# RomWriter.net
KiCad netlist of a schematic drawn in EAGLE
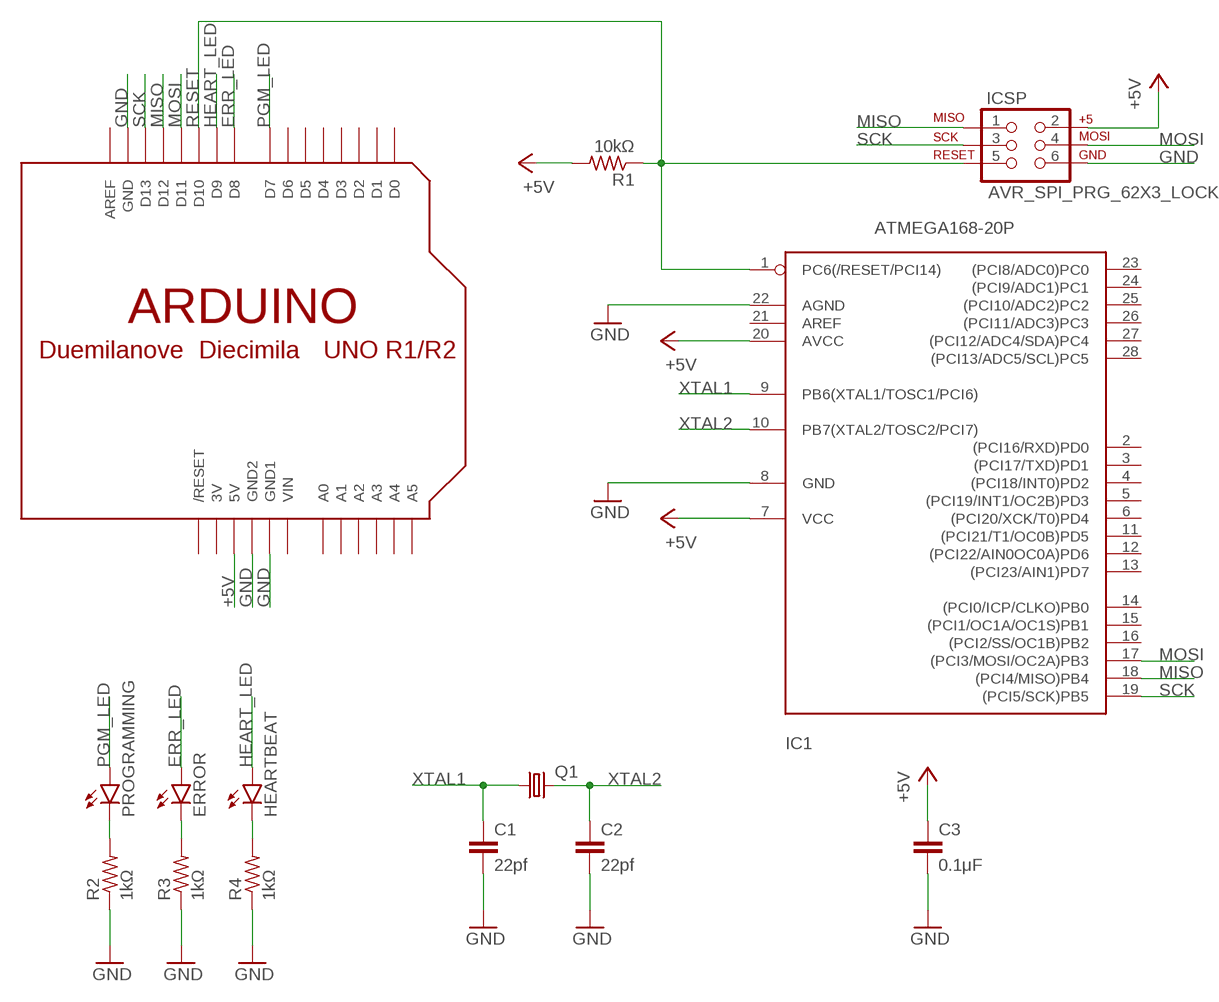
[diagram p0: schematic, sheet 1]

(export (version "E")
  (design (tool "Eeschema 10.0.6"))
  (components
    (comp (ref "C1")
      (value "22pf")
      (footprint "eagle-import:C2.5-2")
      (libsource (lib "eagle-import") (part "C2.5/2"))
    )
    (comp (ref "C2")
      (value "22pf")
      (footprint "eagle-import:C2.5-2")
      (libsource (lib "eagle-import") (part "C2.5/2"))
    )
    (comp (ref "C3")
      (value "0.1μF")
      (footprint "eagle-import:C2.5-2")
      (libsource (lib "eagle-import") (part "C2.5/2"))
    )
    (comp (ref "ERROR")
      (value "LED3MM")
      (footprint "eagle-import:LED3MM")
      (libsource (lib "eagle-import") (part "LED3MM"))
    )
    (comp (ref "HEARTBEAT")
      (value "LED3MM")
      (footprint "eagle-import:LED3MM")
      (libsource (lib "eagle-import") (part "LED3MM"))
    )
    (comp (ref "IC1")
      (value "ATMEGA168-20P")
      (footprint "eagle-import:DIL28-3")
      (libsource (lib "eagle-import") (part "ATMEGA168P-20"))
    )
    (comp (ref "ICSP")
      (value "AVR_SPI_PRG_62X3_LOCK")
      (footprint "eagle-import:2X3_LOCK")
      (libsource (lib "eagle-import") (part "AVR_SPI_PRG_62X3_LOCK"))
    )
    (comp (ref "PROGRAMMING")
      (value "LED3MM")
      (footprint "eagle-import:LED3MM")
      (libsource (lib "eagle-import") (part "LED3MM"))
    )
    (comp (ref "Q1")
      (value "CRYSTALHC49S")
      (footprint "eagle-import:HC49_S")
      (libsource (lib "eagle-import") (part "CRYSTALHC49S"))
    )
    (comp (ref "R1")
      (value "10kΩ")
      (footprint "eagle-import:0805-THM")
      (libsource (lib "eagle-import") (part "FLIPFLOP-RES"))
    )
    (comp (ref "R2")
      (value "1kΩ")
      (footprint "eagle-import:0805-THM")
      (libsource (lib "eagle-import") (part "FLIPFLOP-RES"))
    )
    (comp (ref "R3")
      (value "1kΩ")
      (footprint "eagle-import:0805-THM")
      (libsource (lib "eagle-import") (part "FLIPFLOP-RES"))
    )
    (comp (ref "R4")
      (value "1kΩ")
      (footprint "eagle-import:0805-THM")
      (libsource (lib "eagle-import") (part "FLIPFLOP-RES"))
    )
    (comp (ref "U$1")
      (value "ARDUINO_SHIELD_VER2")
      (footprint "eagle-import:ARDUINO_SHIELD")
      (libsource (lib "eagle-import") (part "ARDUINO_SHIELD_VER2"))
    )
  )
  (nets
    (net (code "1") (name "+5V") (class "Default")
      (node (ref "C3") (pin "1") (pinfunction "1_1") (pintype "passive"))
      (node (ref "IC1") (pin "20") (pinfunction "AVCC_20") (pintype "bidirectional"))
      (node (ref "IC1") (pin "7") (pinfunction "VCC_7") (pintype "bidirectional"))
      (node (ref "ICSP") (pin "2") (pinfunction "2_2") (pintype "passive"))
      (node (ref "R1") (pin "2") (pinfunction "2_2") (pintype "passive"))
      (node (ref "U$1") (pin "5V") (pinfunction "5V_5V") (pintype "power_in"))
    )
    (net (code "2") (name "/3V") (class "Default")
      (node (ref "U$1") (pin "3V") (pinfunction "3V_3V") (pintype "power_in"))
    )
    (net (code "3") (name "/ERR_LED") (class "Default")
      (node (ref "ERROR") (pin "A") (pinfunction "A_A") (pintype "passive"))
      (node (ref "U$1") (pin "D8") (pinfunction "D8_D8") (pintype "bidirectional"))
    )
    (net (code "4") (name "/HEART_LED") (class "Default")
      (node (ref "HEARTBEAT") (pin "A") (pinfunction "A_A") (pintype "passive"))
      (node (ref "U$1") (pin "D9") (pinfunction "D9_D9") (pintype "bidirectional"))
    )
    (net (code "5") (name "/MISO") (class "Default")
      (node (ref "IC1") (pin "18") (pinfunction "(PCI4/MISO)PB4_18") (pintype "bidirectional"))
      (node (ref "ICSP") (pin "1") (pinfunction "1_1") (pintype "passive"))
      (node (ref "U$1") (pin "D12") (pinfunction "D12_D12") (pintype "bidirectional"))
    )
    (net (code "6") (name "/MOSI") (class "Default")
      (node (ref "IC1") (pin "17") (pinfunction "(PCI3/MOSI/OC2A)PB3_17") (pintype "bidirectional"))
      (node (ref "ICSP") (pin "4") (pinfunction "4_4") (pintype "passive"))
      (node (ref "U$1") (pin "D11") (pinfunction "D11_D11") (pintype "bidirectional"))
    )
    (net (code "7") (name "/PGM_LED") (class "Default")
      (node (ref "PROGRAMMING") (pin "A") (pinfunction "A_A") (pintype "passive"))
      (node (ref "U$1") (pin "D7") (pinfunction "D7_D7") (pintype "bidirectional"))
    )
    (net (code "8") (name "/RESET") (class "Default")
      (node (ref "IC1") (pin "1") (pinfunction "PC6(/RESET/PCI14)_1") (pintype "bidirectional"))
      (node (ref "ICSP") (pin "5") (pinfunction "5_5") (pintype "passive"))
      (node (ref "R1") (pin "1") (pinfunction "1_1") (pintype "passive"))
      (node (ref "U$1") (pin "D10") (pinfunction "D10_D10") (pintype "bidirectional"))
    )
    (net (code "9") (name "/SCK") (class "Default")
      (node (ref "IC1") (pin "19") (pinfunction "(PCI5/SCK)PB5_19") (pintype "bidirectional"))
      (node (ref "ICSP") (pin "3") (pinfunction "3_3") (pintype "passive"))
      (node (ref "U$1") (pin "D13") (pinfunction "D13_D13") (pintype "bidirectional"))
    )
    (net (code "10") (name "/VIN") (class "Default")
      (node (ref "U$1") (pin "VIN") (pinfunction "VIN_VIN") (pintype "power_in"))
    )
    (net (code "11") (name "/XTAL1") (class "Default")
      (node (ref "C1") (pin "1") (pinfunction "1_1") (pintype "passive"))
      (node (ref "IC1") (pin "9") (pinfunction "PB6(XTAL1/TOSC1/PCI6)_9") (pintype "bidirectional"))
      (node (ref "Q1") (pin "1") (pinfunction "1_1") (pintype "passive"))
    )
    (net (code "12") (name "/XTAL2") (class "Default")
      (node (ref "C2") (pin "1") (pinfunction "1_1") (pintype "passive"))
      (node (ref "IC1") (pin "10") (pinfunction "PB7(XTAL2/TOSC2/PCI7)_10") (pintype "bidirectional"))
      (node (ref "Q1") (pin "2") (pinfunction "2_2") (pintype "passive"))
    )
    (net (code "13") (name "GND") (class "Default")
      (node (ref "C1") (pin "2") (pinfunction "2_2") (pintype "passive"))
      (node (ref "C2") (pin "2") (pinfunction "2_2") (pintype "passive"))
      (node (ref "C3") (pin "2") (pinfunction "2_2") (pintype "passive"))
      (node (ref "IC1") (pin "22") (pinfunction "AGND_22") (pintype "bidirectional"))
      (node (ref "IC1") (pin "8") (pinfunction "GND_8") (pintype "bidirectional"))
      (node (ref "ICSP") (pin "6") (pinfunction "6_6") (pintype "passive"))
      (node (ref "R2") (pin "1") (pinfunction "1_1") (pintype "passive"))
      (node (ref "R3") (pin "1") (pinfunction "1_1") (pintype "passive"))
      (node (ref "R4") (pin "1") (pinfunction "1_1") (pintype "passive"))
      (node (ref "U$1") (pin "GND") (pinfunction "GND_GND") (pintype "power_in"))
      (node (ref "U$1") (pin "GND1") (pinfunction "GND1_GND1") (pintype "power_in"))
      (node (ref "U$1") (pin "GND2") (pinfunction "GND2_GND2") (pintype "power_in"))
    )
    (net (code "14") (name "Net-(ERROR-C)") (class "Default")
      (node (ref "ERROR") (pin "K") (pinfunction "C_K") (pintype "passive"))
      (node (ref "R3") (pin "2") (pinfunction "2_2") (pintype "passive"))
    )
    (net (code "15") (name "Net-(HEARTBEAT-C)") (class "Default")
      (node (ref "HEARTBEAT") (pin "K") (pinfunction "C_K") (pintype "passive"))
      (node (ref "R4") (pin "2") (pinfunction "2_2") (pintype "passive"))
    )
    (net (code "16") (name "Net-(PROGRAMMING-C)") (class "Default")
      (node (ref "PROGRAMMING") (pin "K") (pinfunction "C_K") (pintype "passive"))
      (node (ref "R2") (pin "2") (pinfunction "2_2") (pintype "passive"))
    )
    (net (code "17") (name "unconnected-(IC1-(PCI0{slash}ICP{slash}CLKO)PB0-Pad14)") (class "Default")
      (node (ref "IC1") (pin "14") (pinfunction "(PCI0/ICP/CLKO)PB0_14") (pintype "bidirectional"))
    )
    (net (code "18") (name "unconnected-(IC1-(PCI1{slash}OC1A{slash}OC1S)PB1-Pad15)") (class "Default")
      (node (ref "IC1") (pin "15") (pinfunction "(PCI1/OC1A/OC1S)PB1_15") (pintype "bidirectional"))
    )
    (net (code "19") (name "unconnected-(IC1-(PCI2{slash}SS{slash}OC1B)PB2-Pad16)") (class "Default")
      (node (ref "IC1") (pin "16") (pinfunction "(PCI2/SS/OC1B)PB2_16") (pintype "bidirectional"))
    )
    (net (code "20") (name "unconnected-(IC1-(PCI8{slash}ADC0)PC0-Pad23)") (class "Default")
      (node (ref "IC1") (pin "23") (pinfunction "(PCI8/ADC0)PC0_23") (pintype "bidirectional"))
    )
    (net (code "21") (name "unconnected-(IC1-(PCI9{slash}ADC1)PC1-Pad24)") (class "Default")
      (node (ref "IC1") (pin "24") (pinfunction "(PCI9/ADC1)PC1_24") (pintype "bidirectional"))
    )
    (net (code "22") (name "unconnected-(IC1-(PCI10{slash}ADC2)PC2-Pad25)") (class "Default")
      (node (ref "IC1") (pin "25") (pinfunction "(PCI10/ADC2)PC2_25") (pintype "bidirectional"))
    )
    (net (code "23") (name "unconnected-(IC1-(PCI11{slash}ADC3)PC3-Pad26)") (class "Default")
      (node (ref "IC1") (pin "26") (pinfunction "(PCI11/ADC3)PC3_26") (pintype "bidirectional"))
    )
    (net (code "24") (name "unconnected-(IC1-(PCI12{slash}ADC4{slash}SDA)PC4-Pad27)") (class "Default")
      (node (ref "IC1") (pin "27") (pinfunction "(PCI12/ADC4/SDA)PC4_27") (pintype "bidirectional"))
    )
    (net (code "25") (name "unconnected-(IC1-(PCI13{slash}ADC5{slash}SCL)PC5-Pad28)") (class "Default")
      (node (ref "IC1") (pin "28") (pinfunction "(PCI13/ADC5/SCL)PC5_28") (pintype "bidirectional"))
    )
    (net (code "26") (name "unconnected-(IC1-(PCI16{slash}RXD)PD0-Pad2)") (class "Default")
      (node (ref "IC1") (pin "2") (pinfunction "(PCI16/RXD)PD0_2") (pintype "bidirectional"))
    )
    (net (code "27") (name "unconnected-(IC1-(PCI17{slash}TXD)PD1-Pad3)") (class "Default")
      (node (ref "IC1") (pin "3") (pinfunction "(PCI17/TXD)PD1_3") (pintype "bidirectional"))
    )
    (net (code "28") (name "unconnected-(IC1-(PCI18{slash}INT0)PD2-Pad4)") (class "Default")
      (node (ref "IC1") (pin "4") (pinfunction "(PCI18/INT0)PD2_4") (pintype "bidirectional"))
    )
    (net (code "29") (name "unconnected-(IC1-(PCI19{slash}INT1{slash}OC2B)PD3-Pad5)") (class "Default")
      (node (ref "IC1") (pin "5") (pinfunction "(PCI19/INT1/OC2B)PD3_5") (pintype "bidirectional"))
    )
    (net (code "30") (name "unconnected-(IC1-(PCI20{slash}XCK{slash}T0)PD4-Pad6)") (class "Default")
      (node (ref "IC1") (pin "6") (pinfunction "(PCI20/XCK/T0)PD4_6") (pintype "bidirectional"))
    )
    (net (code "31") (name "unconnected-(IC1-(PCI21{slash}T1{slash}OC0B)PD5-Pad11)") (class "Default")
      (node (ref "IC1") (pin "11") (pinfunction "(PCI21/T1/OC0B)PD5_11") (pintype "bidirectional"))
    )
    (net (code "32") (name "unconnected-(IC1-(PCI22{slash}AIN0OC0A)PD6-Pad12)") (class "Default")
      (node (ref "IC1") (pin "12") (pinfunction "(PCI22/AIN0OC0A)PD6_12") (pintype "bidirectional"))
    )
    (net (code "33") (name "unconnected-(IC1-(PCI23{slash}AIN1)PD7-Pad13)") (class "Default")
      (node (ref "IC1") (pin "13") (pinfunction "(PCI23/AIN1)PD7_13") (pintype "bidirectional"))
    )
    (net (code "34") (name "unconnected-(IC1-AREF-Pad21)") (class "Default")
      (node (ref "IC1") (pin "21") (pinfunction "AREF_21") (pintype "bidirectional"))
    )
    (net (code "35") (name "unconnected-(U$1-PadA0)") (class "Default")
      (node (ref "U$1") (pin "A0") (pinfunction "A0_A0") (pintype "bidirectional"))
    )
    (net (code "36") (name "unconnected-(U$1-PadA1)") (class "Default")
      (node (ref "U$1") (pin "A1") (pinfunction "A1_A1") (pintype "bidirectional"))
    )
    (net (code "37") (name "unconnected-(U$1-PadA2)") (class "Default")
      (node (ref "U$1") (pin "A2") (pinfunction "A2_A2") (pintype "bidirectional"))
    )
    (net (code "38") (name "unconnected-(U$1-PadA3)") (class "Default")
      (node (ref "U$1") (pin "A3") (pinfunction "A3_A3") (pintype "bidirectional"))
    )
    (net (code "39") (name "unconnected-(U$1-PadA4)") (class "Default")
      (node (ref "U$1") (pin "A4") (pinfunction "A4_A4") (pintype "bidirectional"))
    )
    (net (code "40") (name "unconnected-(U$1-PadA5)") (class "Default")
      (node (ref "U$1") (pin "A5") (pinfunction "A5_A5") (pintype "bidirectional"))
    )
    (net (code "41") (name "unconnected-(U$1-PadAREF)") (class "Default")
      (node (ref "U$1") (pin "AREF") (pinfunction "AREF_AREF") (pintype "bidirectional"))
    )
    (net (code "42") (name "unconnected-(U$1-PadD0)") (class "Default")
      (node (ref "U$1") (pin "D0") (pinfunction "D0_D0") (pintype "bidirectional"))
    )
    (net (code "43") (name "unconnected-(U$1-PadD1)") (class "Default")
      (node (ref "U$1") (pin "D1") (pinfunction "D1_D1") (pintype "bidirectional"))
    )
    (net (code "44") (name "unconnected-(U$1-PadD2)") (class "Default")
      (node (ref "U$1") (pin "D2") (pinfunction "D2_D2") (pintype "bidirectional"))
    )
    (net (code "45") (name "unconnected-(U$1-PadD3)") (class "Default")
      (node (ref "U$1") (pin "D3") (pinfunction "D3_D3") (pintype "bidirectional"))
    )
    (net (code "46") (name "unconnected-(U$1-PadD4)") (class "Default")
      (node (ref "U$1") (pin "D4") (pinfunction "D4_D4") (pintype "bidirectional"))
    )
    (net (code "47") (name "unconnected-(U$1-PadD5)") (class "Default")
      (node (ref "U$1") (pin "D5") (pinfunction "D5_D5") (pintype "bidirectional"))
    )
    (net (code "48") (name "unconnected-(U$1-PadD6)") (class "Default")
      (node (ref "U$1") (pin "D6") (pinfunction "D6_D6") (pintype "bidirectional"))
    )
    (net (code "49") (name "unconnected-(U$1-{slash}RESET-PadRESET)") (class "Default")
      (node (ref "U$1") (pin "RESET") (pinfunction "/RESET_RESET") (pintype "bidirectional"))
    )
  )
)
